# 780-00012-P1_rev3_Sch_M2_Focus_Drive.net
KiCad netlist of a schematic drawn in Altium Designer
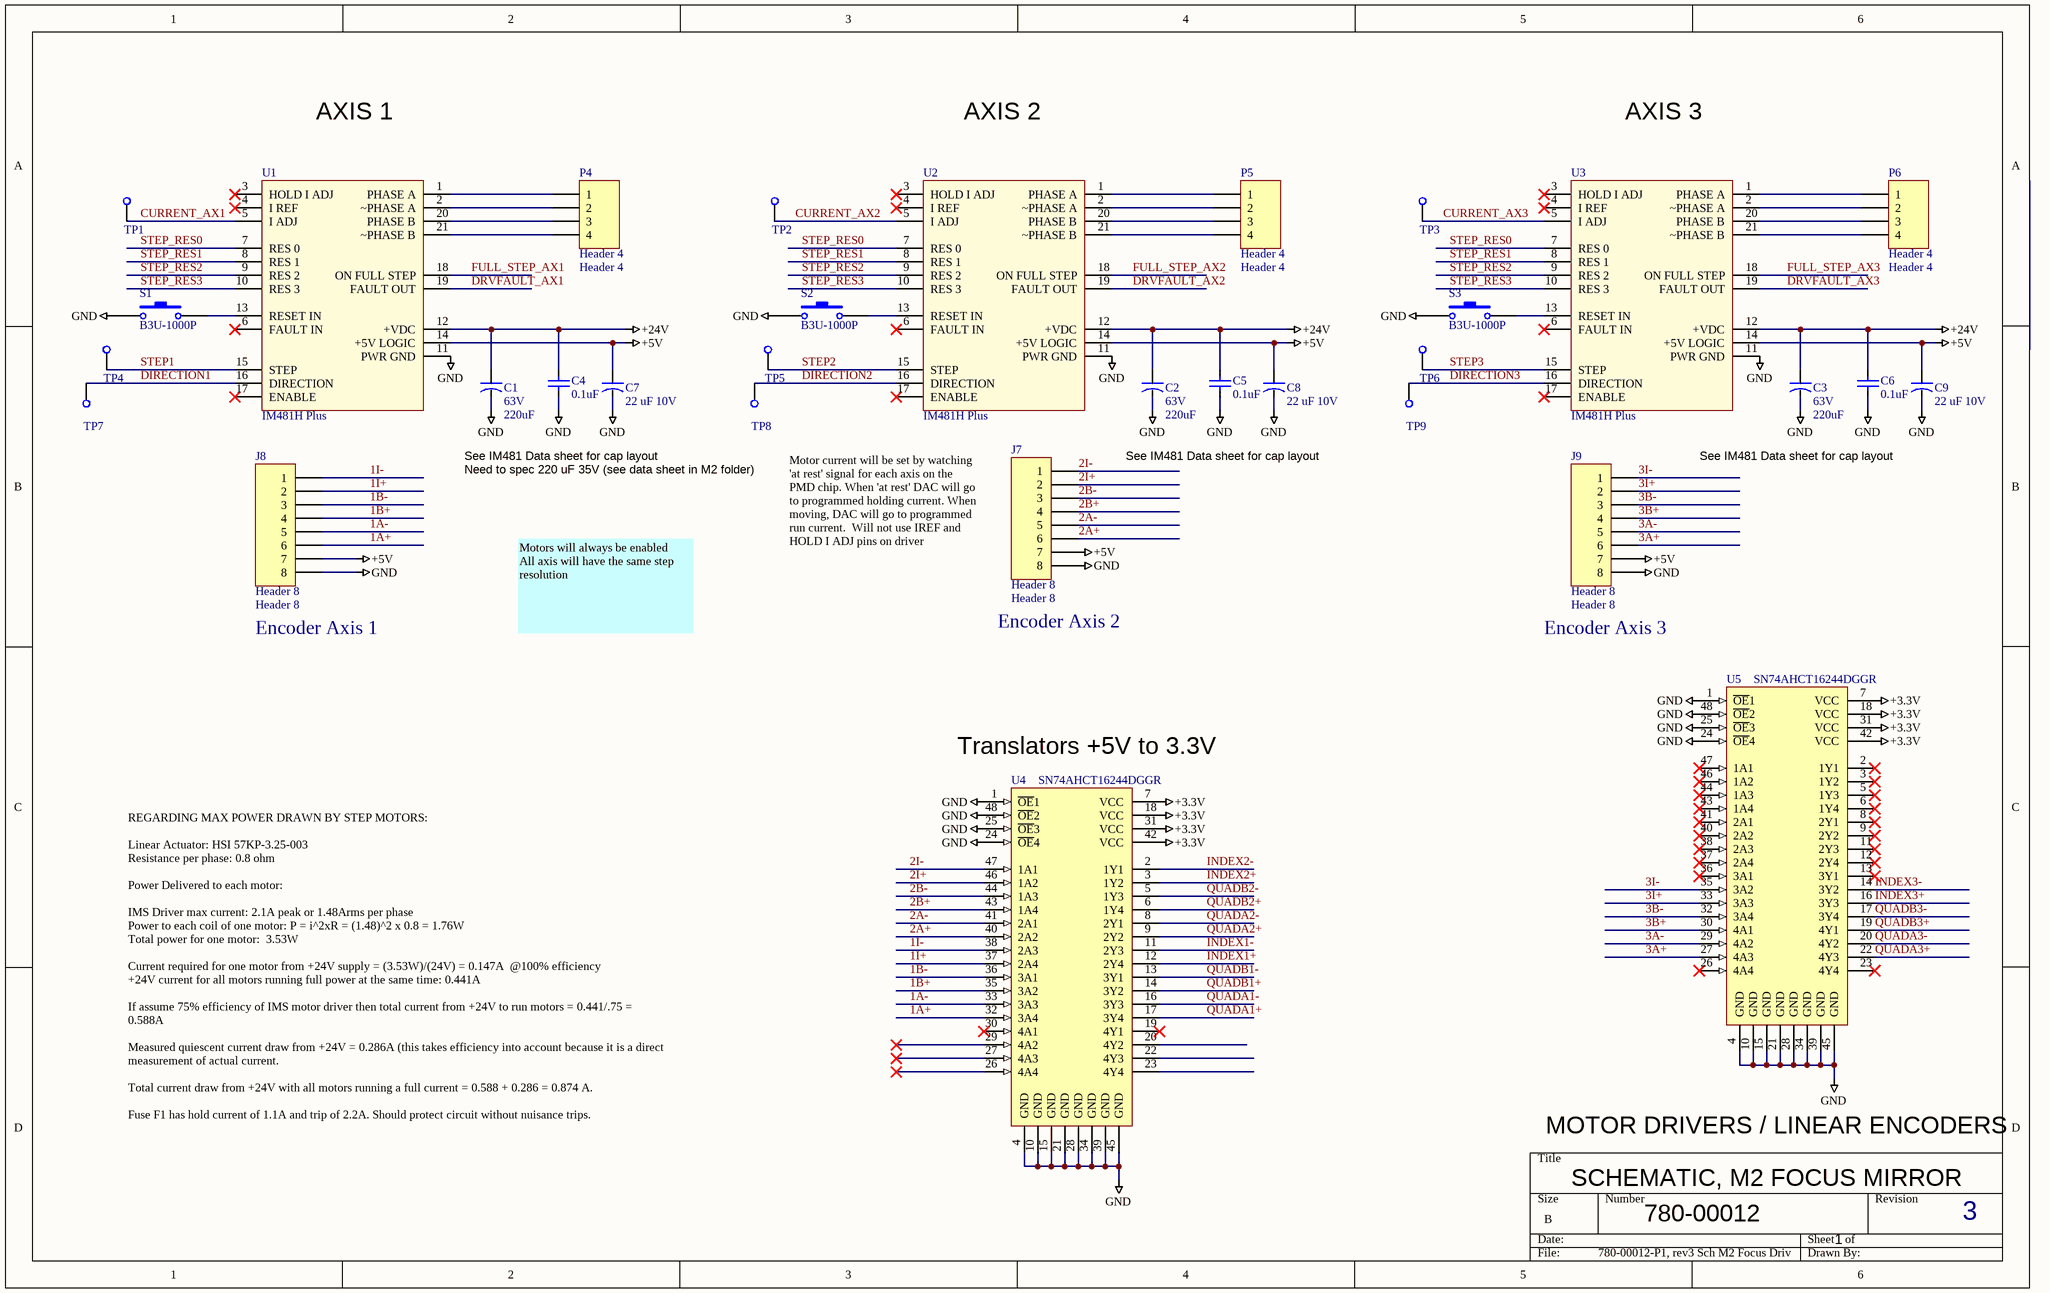
[diagram p0: 780-00012-P1, rev3 Sch M2 Focus Drive.SchDoc]

(export (version "E")
  (design (tool "Eeschema 10.0.6"))
  (components
    (comp (ref "C1")
      (value "63V")
      (footprint "CAP 220uF 63V")
      (description "CAP 220UF 63V ELECT MVH SMD")
      (fields (field (name "MANUFACTURER") "United Chemi-Con") (field (name "ALTIUM_VALUE") "220uF"))
      (libsource (lib "Richs Schematic Components") (part "Cap 220uF, 63V"))
    )
    (comp (ref "C2")
      (value "63V")
      (footprint "CAP 220uF 63V")
      (description "CAP 220UF 63V ELECT MVH SMD")
      (fields (field (name "MANUFACTURER") "United Chemi-Con") (field (name "ALTIUM_VALUE") "220uF"))
      (libsource (lib "Richs Schematic Components") (part "Cap 220uF, 63V"))
    )
    (comp (ref "C3")
      (value "63V")
      (footprint "CAP 220uF 63V")
      (description "CAP 220UF 63V ELECT MVH SMD")
      (fields (field (name "MANUFACTURER") "United Chemi-Con") (field (name "ALTIUM_VALUE") "220uF"))
      (libsource (lib "Richs Schematic Components") (part "Cap 220uF, 63V"))
    )
    (comp (ref "C4")
      (value "0.1uF")
      (footprint "SMD_0805")
      (description "Capacitor")
      (fields (field (name "Comment") "Cap SMD"))
      (libsource (lib "Richs Schematic Components") (part "Cap SMD"))
    )
    (comp (ref "C5")
      (value "0.1uF")
      (footprint "SMD_0805")
      (description "Capacitor")
      (fields (field (name "Comment") "Cap SMD"))
      (libsource (lib "Richs Schematic Components") (part "Cap SMD"))
    )
    (comp (ref "C6")
      (value "0.1uF")
      (footprint "SMD_0805")
      (description "Capacitor")
      (fields (field (name "Comment") "Cap SMD"))
      (libsource (lib "Richs Schematic Components") (part "Cap SMD"))
    )
    (comp (ref "C7")
      (value "22 uF 10V")
      (footprint "SMD_CAP_3216")
      (description "outline 3.2mm x 1.6mm")
      (fields (field (name "MANUFACTURER") "KEMET") (field (name "Comment") "16V"))
      (libsource (lib "Richs Schematic Components") (part "Cap Tant 16V"))
    )
    (comp (ref "C8")
      (value "22 uF 10V")
      (footprint "SMD_CAP_3216")
      (description "outline 3.2mm x 1.6mm")
      (fields (field (name "MANUFACTURER") "KEMET") (field (name "Comment") "16V"))
      (libsource (lib "Richs Schematic Components") (part "Cap Tant 16V"))
    )
    (comp (ref "C9")
      (value "22 uF 10V")
      (footprint "SMD_CAP_3216")
      (description "outline 3.2mm x 1.6mm")
      (fields (field (name "MANUFACTURER") "KEMET") (field (name "Comment") "16V"))
      (libsource (lib "Richs Schematic Components") (part "Cap Tant 16V"))
    )
    (comp (ref "J7")
      (value "Header 8")
      (footprint "HDR1X8 for IDC")
      (description "Header, 8-Pin")
      (fields (field (name "ALTIUM_VALUE") "Header 8"))
      (libsource (lib "Richs Schematic Components") (part "Header 8"))
    )
    (comp (ref "J8")
      (value "Header 8")
      (footprint "HDR1X8 for IDC")
      (description "Header, 8-Pin")
      (fields (field (name "ALTIUM_VALUE") "Header 8"))
      (libsource (lib "Richs Schematic Components") (part "Header 8"))
    )
    (comp (ref "J9")
      (value "Header 8")
      (footprint "HDR1X8 for IDC")
      (description "Header, 8-Pin")
      (fields (field (name "ALTIUM_VALUE") "Header 8"))
      (libsource (lib "Richs Schematic Components") (part "Header 8"))
    )
    (comp (ref "P4")
      (value "Header 4")
      (footprint "HDR1X4 for IDC")
      (description "Header, 4-Pin")
      (fields (field (name "ALTIUM_VALUE") "Header 4"))
      (libsource (lib "Richs Schematic Components") (part "Header 4"))
    )
    (comp (ref "P5")
      (value "Header 4")
      (footprint "HDR1X4 for IDC")
      (description "Header, 4-Pin")
      (fields (field (name "ALTIUM_VALUE") "Header 4"))
      (libsource (lib "Richs Schematic Components") (part "Header 4"))
    )
    (comp (ref "P6")
      (value "Header 4")
      (footprint "HDR1X4 for IDC")
      (description "Header, 4-Pin")
      (fields (field (name "ALTIUM_VALUE") "Header 4"))
      (libsource (lib "Richs Schematic Components") (part "Header 4"))
    )
    (comp (ref "S1")
      (value "B3U-1000P")
      (footprint "B3U-1000P")
      (description "Switch")
      (fields (field (name "MANUFACTURER") "Omron Electronics"))
      (libsource (lib "Miscellaneous Devices") (part "SW-PB"))
    )
    (comp (ref "S2")
      (value "B3U-1000P")
      (footprint "B3U-1000P")
      (description "Switch")
      (fields (field (name "MANUFACTURER") "Omron Electronics"))
      (libsource (lib "Miscellaneous Devices") (part "SW-PB"))
    )
    (comp (ref "S3")
      (value "B3U-1000P")
      (footprint "B3U-1000P")
      (description "Switch")
      (fields (field (name "MANUFACTURER") "Omron Electronics"))
      (libsource (lib "Miscellaneous Devices") (part "SW-PB"))
    )
    (comp (ref "TP1")
      (value "Test Point SMD")
      (footprint "SMD_TEST POINT")
      (description "SMD loop test point")
      (libsource (lib "Richs Schematic Components") (part "Test Point SMD"))
    )
    (comp (ref "TP2")
      (value "Test Point SMD")
      (footprint "SMD_TEST POINT")
      (description "SMD loop test point")
      (libsource (lib "Richs Schematic Components") (part "Test Point SMD"))
    )
    (comp (ref "TP3")
      (value "Test Point SMD")
      (footprint "SMD_TEST POINT")
      (description "SMD loop test point")
      (libsource (lib "Richs Schematic Components") (part "Test Point SMD"))
    )
    (comp (ref "TP4")
      (value "Test Point SMD")
      (footprint "SMD_TEST POINT")
      (description "SMD loop test point")
      (libsource (lib "Richs Schematic Components") (part "Test Point SMD"))
    )
    (comp (ref "TP5")
      (value "Test Point SMD")
      (footprint "SMD_TEST POINT")
      (description "SMD loop test point")
      (libsource (lib "Richs Schematic Components") (part "Test Point SMD"))
    )
    (comp (ref "TP6")
      (value "Test Point SMD")
      (footprint "SMD_TEST POINT")
      (description "SMD loop test point")
      (libsource (lib "Richs Schematic Components") (part "Test Point SMD"))
    )
    (comp (ref "TP7")
      (value "Test Point SMD")
      (footprint "SMD_TEST POINT")
      (description "SMD loop test point")
      (libsource (lib "Richs Schematic Components") (part "Test Point SMD"))
    )
    (comp (ref "TP8")
      (value "Test Point SMD")
      (footprint "SMD_TEST POINT")
      (description "SMD loop test point")
      (libsource (lib "Richs Schematic Components") (part "Test Point SMD"))
    )
    (comp (ref "TP9")
      (value "Test Point SMD")
      (footprint "SMD_TEST POINT")
      (description "SMD loop test point")
      (libsource (lib "Richs Schematic Components") (part "Test Point SMD"))
    )
    (comp (ref "U1")
      (value "IM481H Plus")
      (footprint "IM481H Vertical")
      (description "Hybrid stepper motor driver")
      (libsource (lib "Richs Schematic Components") (part "IM481H Plus"))
    )
    (comp (ref "U2")
      (value "IM481H Plus")
      (footprint "IM481H Vertical")
      (description "Hybrid stepper motor driver")
      (libsource (lib "Richs Schematic Components") (part "IM481H Plus"))
    )
    (comp (ref "U3")
      (value "IM481H Plus")
      (footprint "IM481H Vertical")
      (description "Hybrid stepper motor driver")
      (libsource (lib "Richs Schematic Components") (part "IM481H Plus"))
    )
    (comp (ref "U4")
      (value "SN74AHCT16244DGGR")
      (footprint "DGG048_N")
      (description "16-Bit Buffer/Driver with 3-State Outputs")
      (libsource (lib "TI Logic Buffer Line Driver") (part "SN74AHCT16244DGGR"))
    )
    (comp (ref "U5")
      (value "SN74AHCT16244DGGR")
      (footprint "DGG048_N")
      (description "16-Bit Buffer/Driver with 3-State Outputs")
      (libsource (lib "TI Logic Buffer Line Driver") (part "SN74AHCT16244DGGR"))
    )
  )
  (nets
    (net (code "1") (name "+3.3V") (class "Default")
      (node (ref "U4") (pin "18") (pinfunction "VCC_18") (pintype "power_in"))
      (node (ref "U4") (pin "31") (pinfunction "VCC_31") (pintype "power_in"))
      (node (ref "U4") (pin "42") (pinfunction "VCC_42") (pintype "power_in"))
      (node (ref "U4") (pin "7") (pinfunction "VCC_7") (pintype "power_in"))
      (node (ref "U5") (pin "18") (pinfunction "VCC_18") (pintype "power_in"))
      (node (ref "U5") (pin "31") (pinfunction "VCC_31") (pintype "power_in"))
      (node (ref "U5") (pin "42") (pinfunction "VCC_42") (pintype "power_in"))
      (node (ref "U5") (pin "7") (pinfunction "VCC_7") (pintype "power_in"))
    )
    (net (code "2") (name "+5V") (class "Default")
      (node (ref "C7") (pin "1") (pinfunction "1_1") (pintype "passive"))
      (node (ref "C8") (pin "1") (pinfunction "1_1") (pintype "passive"))
      (node (ref "C9") (pin "1") (pinfunction "1_1") (pintype "passive"))
      (node (ref "J7") (pin "7") (pinfunction "7_7") (pintype "passive"))
      (node (ref "J8") (pin "7") (pinfunction "7_7") (pintype "passive"))
      (node (ref "J9") (pin "7") (pinfunction "7_7") (pintype "passive"))
      (node (ref "U1") (pin "14") (pinfunction "+5V_LOGIC_14") (pintype "passive"))
      (node (ref "U2") (pin "14") (pinfunction "+5V_LOGIC_14") (pintype "passive"))
      (node (ref "U3") (pin "14") (pinfunction "+5V_LOGIC_14") (pintype "passive"))
    )
    (net (code "3") (name "+24V") (class "Default")
      (node (ref "C1") (pin "1") (pinfunction "1_1") (pintype "passive"))
      (node (ref "C2") (pin "1") (pinfunction "1_1") (pintype "passive"))
      (node (ref "C3") (pin "1") (pinfunction "1_1") (pintype "passive"))
      (node (ref "C4") (pin "2") (pinfunction "2_2") (pintype "passive"))
      (node (ref "C5") (pin "2") (pinfunction "2_2") (pintype "passive"))
      (node (ref "C6") (pin "2") (pinfunction "2_2") (pintype "passive"))
      (node (ref "U1") (pin "12") (pinfunction "+VDC_12") (pintype "passive"))
      (node (ref "U2") (pin "12") (pinfunction "+VDC_12") (pintype "passive"))
      (node (ref "U3") (pin "12") (pinfunction "+VDC_12") (pintype "passive"))
    )
    (net (code "4") (name "/1A+") (class "Default")
      (node (ref "J8") (pin "6") (pinfunction "6_6") (pintype "passive"))
      (node (ref "U4") (pin "32") (pinfunction "3A4_32") (pintype "input"))
    )
    (net (code "5") (name "/1A-") (class "Default")
      (node (ref "J8") (pin "5") (pinfunction "5_5") (pintype "passive"))
      (node (ref "U4") (pin "33") (pinfunction "3A3_33") (pintype "input"))
    )
    (net (code "6") (name "/1B+") (class "Default")
      (node (ref "J8") (pin "4") (pinfunction "4_4") (pintype "passive"))
      (node (ref "U4") (pin "35") (pinfunction "3A2_35") (pintype "input"))
    )
    (net (code "7") (name "/1B-") (class "Default")
      (node (ref "J8") (pin "3") (pinfunction "3_3") (pintype "passive"))
      (node (ref "U4") (pin "36") (pinfunction "3A1_36") (pintype "input"))
    )
    (net (code "8") (name "/1I+") (class "Default")
      (node (ref "J8") (pin "2") (pinfunction "2_2") (pintype "passive"))
      (node (ref "U4") (pin "37") (pinfunction "2A4_37") (pintype "input"))
    )
    (net (code "9") (name "/1I-") (class "Default")
      (node (ref "J8") (pin "1") (pinfunction "1_1") (pintype "passive"))
      (node (ref "U4") (pin "38") (pinfunction "2A3_38") (pintype "input"))
    )
    (net (code "10") (name "/2A+") (class "Default")
      (node (ref "J7") (pin "6") (pinfunction "6_6") (pintype "passive"))
      (node (ref "U4") (pin "40") (pinfunction "2A2_40") (pintype "input"))
    )
    (net (code "11") (name "/2A-") (class "Default")
      (node (ref "J7") (pin "5") (pinfunction "5_5") (pintype "passive"))
      (node (ref "U4") (pin "41") (pinfunction "2A1_41") (pintype "input"))
    )
    (net (code "12") (name "/2B+") (class "Default")
      (node (ref "J7") (pin "4") (pinfunction "4_4") (pintype "passive"))
      (node (ref "U4") (pin "43") (pinfunction "1A4_43") (pintype "input"))
    )
    (net (code "13") (name "/2B-") (class "Default")
      (node (ref "J7") (pin "3") (pinfunction "3_3") (pintype "passive"))
      (node (ref "U4") (pin "44") (pinfunction "1A3_44") (pintype "input"))
    )
    (net (code "14") (name "/2I+") (class "Default")
      (node (ref "J7") (pin "2") (pinfunction "2_2") (pintype "passive"))
      (node (ref "U4") (pin "46") (pinfunction "1A2_46") (pintype "input"))
    )
    (net (code "15") (name "/2I-") (class "Default")
      (node (ref "J7") (pin "1") (pinfunction "1_1") (pintype "passive"))
      (node (ref "U4") (pin "47") (pinfunction "1A1_47") (pintype "input"))
    )
    (net (code "16") (name "/3A+") (class "Default")
      (node (ref "J9") (pin "6") (pinfunction "6_6") (pintype "passive"))
      (node (ref "U5") (pin "27") (pinfunction "4A3_27") (pintype "input"))
    )
    (net (code "17") (name "/3A-") (class "Default")
      (node (ref "J9") (pin "5") (pinfunction "5_5") (pintype "passive"))
      (node (ref "U5") (pin "29") (pinfunction "4A2_29") (pintype "input"))
    )
    (net (code "18") (name "/3B+") (class "Default")
      (node (ref "J9") (pin "4") (pinfunction "4_4") (pintype "passive"))
      (node (ref "U5") (pin "30") (pinfunction "4A1_30") (pintype "input"))
    )
    (net (code "19") (name "/3B-") (class "Default")
      (node (ref "J9") (pin "3") (pinfunction "3_3") (pintype "passive"))
      (node (ref "U5") (pin "32") (pinfunction "3A4_32") (pintype "input"))
    )
    (net (code "20") (name "/3I+") (class "Default")
      (node (ref "J9") (pin "2") (pinfunction "2_2") (pintype "passive"))
      (node (ref "U5") (pin "33") (pinfunction "3A3_33") (pintype "input"))
    )
    (net (code "21") (name "/3I-") (class "Default")
      (node (ref "J9") (pin "1") (pinfunction "1_1") (pintype "passive"))
      (node (ref "U5") (pin "35") (pinfunction "3A2_35") (pintype "input"))
    )
    (net (code "22") (name "/CURRENT_AX1") (class "Default")
      (node (ref "TP1") (pin "1") (pinfunction "TP_1") (pintype "passive"))
      (node (ref "U1") (pin "5") (pinfunction "I_ADJ_5") (pintype "passive"))
    )
    (net (code "23") (name "/CURRENT_AX2") (class "Default")
      (node (ref "TP2") (pin "1") (pinfunction "TP_1") (pintype "passive"))
      (node (ref "U2") (pin "5") (pinfunction "I_ADJ_5") (pintype "passive"))
    )
    (net (code "24") (name "/CURRENT_AX3") (class "Default")
      (node (ref "TP3") (pin "1") (pinfunction "TP_1") (pintype "passive"))
      (node (ref "U3") (pin "5") (pinfunction "I_ADJ_5") (pintype "passive"))
    )
    (net (code "25") (name "/DIRECTION1") (class "Default")
      (node (ref "TP7") (pin "1") (pinfunction "TP_1") (pintype "passive"))
      (node (ref "U1") (pin "16") (pinfunction "DIRECTION_16") (pintype "passive"))
    )
    (net (code "26") (name "/DIRECTION2") (class "Default")
      (node (ref "TP8") (pin "1") (pinfunction "TP_1") (pintype "passive"))
      (node (ref "U2") (pin "16") (pinfunction "DIRECTION_16") (pintype "passive"))
    )
    (net (code "27") (name "/DIRECTION3") (class "Default")
      (node (ref "TP9") (pin "1") (pinfunction "TP_1") (pintype "passive"))
      (node (ref "U3") (pin "16") (pinfunction "DIRECTION_16") (pintype "passive"))
    )
    (net (code "28") (name "/DRVFAULT_AX1") (class "Default")
      (node (ref "U1") (pin "19") (pinfunction "FAULT_OUT_19") (pintype "passive"))
    )
    (net (code "29") (name "/DRVFAULT_AX2") (class "Default")
      (node (ref "U2") (pin "19") (pinfunction "FAULT_OUT_19") (pintype "passive"))
    )
    (net (code "30") (name "/DRVFAULT_AX3") (class "Default")
      (node (ref "U3") (pin "19") (pinfunction "FAULT_OUT_19") (pintype "passive"))
    )
    (net (code "31") (name "/FULL_STEP_AX1") (class "Default")
      (node (ref "U1") (pin "18") (pinfunction "ON_FULL_STEP_18") (pintype "passive"))
    )
    (net (code "32") (name "/FULL_STEP_AX2") (class "Default")
      (node (ref "U2") (pin "18") (pinfunction "ON_FULL_STEP_18") (pintype "passive"))
    )
    (net (code "33") (name "/FULL_STEP_AX3") (class "Default")
      (node (ref "U3") (pin "18") (pinfunction "ON_FULL_STEP_18") (pintype "passive"))
    )
    (net (code "34") (name "/INDEX1+") (class "Default")
      (node (ref "U4") (pin "12") (pinfunction "2Y4_12") (pintype "tri_state"))
    )
    (net (code "35") (name "/INDEX1-") (class "Default")
      (node (ref "U4") (pin "11") (pinfunction "2Y3_11") (pintype "tri_state"))
    )
    (net (code "36") (name "/INDEX2+") (class "Default")
      (node (ref "U4") (pin "3") (pinfunction "1Y2_3") (pintype "tri_state"))
    )
    (net (code "37") (name "/INDEX2-") (class "Default")
      (node (ref "U4") (pin "2") (pinfunction "1Y1_2") (pintype "tri_state"))
    )
    (net (code "38") (name "/INDEX3+") (class "Default")
      (node (ref "U5") (pin "16") (pinfunction "3Y3_16") (pintype "tri_state"))
    )
    (net (code "39") (name "/INDEX3-") (class "Default")
      (node (ref "U5") (pin "14") (pinfunction "3Y2_14") (pintype "tri_state"))
    )
    (net (code "40") (name "/QUADA1+") (class "Default")
      (node (ref "U4") (pin "17") (pinfunction "3Y4_17") (pintype "tri_state"))
    )
    (net (code "41") (name "/QUADA1-") (class "Default")
      (node (ref "U4") (pin "16") (pinfunction "3Y3_16") (pintype "tri_state"))
    )
    (net (code "42") (name "/QUADA2+") (class "Default")
      (node (ref "U4") (pin "9") (pinfunction "2Y2_9") (pintype "tri_state"))
    )
    (net (code "43") (name "/QUADA2-") (class "Default")
      (node (ref "U4") (pin "8") (pinfunction "2Y1_8") (pintype "tri_state"))
    )
    (net (code "44") (name "/QUADA3+") (class "Default")
      (node (ref "U5") (pin "22") (pinfunction "4Y3_22") (pintype "tri_state"))
    )
    (net (code "45") (name "/QUADA3-") (class "Default")
      (node (ref "U5") (pin "20") (pinfunction "4Y2_20") (pintype "tri_state"))
    )
    (net (code "46") (name "/QUADB1+") (class "Default")
      (node (ref "U4") (pin "14") (pinfunction "3Y2_14") (pintype "tri_state"))
    )
    (net (code "47") (name "/QUADB1-") (class "Default")
      (node (ref "U4") (pin "13") (pinfunction "3Y1_13") (pintype "tri_state"))
    )
    (net (code "48") (name "/QUADB2+") (class "Default")
      (node (ref "U4") (pin "6") (pinfunction "1Y4_6") (pintype "tri_state"))
    )
    (net (code "49") (name "/QUADB2-") (class "Default")
      (node (ref "U4") (pin "5") (pinfunction "1Y3_5") (pintype "tri_state"))
    )
    (net (code "50") (name "/QUADB3+") (class "Default")
      (node (ref "U5") (pin "19") (pinfunction "4Y1_19") (pintype "tri_state"))
    )
    (net (code "51") (name "/QUADB3-") (class "Default")
      (node (ref "U5") (pin "17") (pinfunction "3Y4_17") (pintype "tri_state"))
    )
    (net (code "52") (name "/STEP1") (class "Default")
      (node (ref "TP4") (pin "1") (pinfunction "TP_1") (pintype "passive"))
      (node (ref "U1") (pin "15") (pinfunction "STEP_15") (pintype "passive"))
    )
    (net (code "53") (name "/STEP2") (class "Default")
      (node (ref "TP5") (pin "1") (pinfunction "TP_1") (pintype "passive"))
      (node (ref "U2") (pin "15") (pinfunction "STEP_15") (pintype "passive"))
    )
    (net (code "54") (name "/STEP3") (class "Default")
      (node (ref "TP6") (pin "1") (pinfunction "TP_1") (pintype "passive"))
      (node (ref "U3") (pin "15") (pinfunction "STEP_15") (pintype "passive"))
    )
    (net (code "55") (name "/STEP_RES0") (class "Default")
      (node (ref "U1") (pin "7") (pinfunction "RES_0_7") (pintype "passive"))
      (node (ref "U2") (pin "7") (pinfunction "RES_0_7") (pintype "passive"))
      (node (ref "U3") (pin "7") (pinfunction "RES_0_7") (pintype "passive"))
    )
    (net (code "56") (name "/STEP_RES1") (class "Default")
      (node (ref "U1") (pin "8") (pinfunction "RES_1_8") (pintype "passive"))
      (node (ref "U2") (pin "8") (pinfunction "RES_1_8") (pintype "passive"))
      (node (ref "U3") (pin "8") (pinfunction "RES_1_8") (pintype "passive"))
    )
    (net (code "57") (name "/STEP_RES2") (class "Default")
      (node (ref "U1") (pin "9") (pinfunction "RES_2_9") (pintype "passive"))
      (node (ref "U2") (pin "9") (pinfunction "RES_2_9") (pintype "passive"))
      (node (ref "U3") (pin "9") (pinfunction "RES_2_9") (pintype "passive"))
    )
    (net (code "58") (name "/STEP_RES3") (class "Default")
      (node (ref "U1") (pin "10") (pinfunction "RES_3_10") (pintype "passive"))
      (node (ref "U2") (pin "10") (pinfunction "RES_3_10") (pintype "passive"))
      (node (ref "U3") (pin "10") (pinfunction "RES_3_10") (pintype "passive"))
    )
    (net (code "59") (name "GND") (class "Default")
      (node (ref "C1") (pin "2") (pinfunction "2_2") (pintype "passive"))
      (node (ref "C2") (pin "2") (pinfunction "2_2") (pintype "passive"))
      (node (ref "C3") (pin "2") (pinfunction "2_2") (pintype "passive"))
      (node (ref "C4") (pin "1") (pinfunction "1_1") (pintype "passive"))
      (node (ref "C5") (pin "1") (pinfunction "1_1") (pintype "passive"))
      (node (ref "C6") (pin "1") (pinfunction "1_1") (pintype "passive"))
      (node (ref "C7") (pin "2") (pinfunction "2_2") (pintype "passive"))
      (node (ref "C8") (pin "2") (pinfunction "2_2") (pintype "passive"))
      (node (ref "C9") (pin "2") (pinfunction "2_2") (pintype "passive"))
      (node (ref "J7") (pin "8") (pinfunction "8_8") (pintype "passive"))
      (node (ref "J8") (pin "8") (pinfunction "8_8") (pintype "passive"))
      (node (ref "J9") (pin "8") (pinfunction "8_8") (pintype "passive"))
      (node (ref "S1") (pin "1") (pinfunction "1_1") (pintype "passive"))
      (node (ref "S2") (pin "1") (pinfunction "1_1") (pintype "passive"))
      (node (ref "S3") (pin "1") (pinfunction "1_1") (pintype "passive"))
      (node (ref "U1") (pin "11") (pinfunction "PWR_GND_11") (pintype "passive"))
      (node (ref "U2") (pin "11") (pinfunction "PWR_GND_11") (pintype "passive"))
      (node (ref "U3") (pin "11") (pinfunction "PWR_GND_11") (pintype "passive"))
      (node (ref "U4") (pin "1") (pinfunction "~{OE}1_1") (pintype "input"))
      (node (ref "U4") (pin "10") (pinfunction "GND_10") (pintype "power_in"))
      (node (ref "U4") (pin "15") (pinfunction "GND_15") (pintype "power_in"))
      (node (ref "U4") (pin "21") (pinfunction "GND_21") (pintype "power_in"))
      (node (ref "U4") (pin "24") (pinfunction "~{OE}4_24") (pintype "input"))
      (node (ref "U4") (pin "25") (pinfunction "~{OE}3_25") (pintype "input"))
      (node (ref "U4") (pin "28") (pinfunction "GND_28") (pintype "power_in"))
      (node (ref "U4") (pin "34") (pinfunction "GND_34") (pintype "power_in"))
      (node (ref "U4") (pin "39") (pinfunction "GND_39") (pintype "power_in"))
      (node (ref "U4") (pin "4") (pinfunction "GND_4") (pintype "power_in"))
      (node (ref "U4") (pin "45") (pinfunction "GND_45") (pintype "power_in"))
      (node (ref "U4") (pin "48") (pinfunction "~{OE}2_48") (pintype "input"))
      (node (ref "U5") (pin "1") (pinfunction "~{OE}1_1") (pintype "input"))
      (node (ref "U5") (pin "10") (pinfunction "GND_10") (pintype "power_in"))
      (node (ref "U5") (pin "15") (pinfunction "GND_15") (pintype "power_in"))
      (node (ref "U5") (pin "21") (pinfunction "GND_21") (pintype "power_in"))
      (node (ref "U5") (pin "24") (pinfunction "~{OE}4_24") (pintype "input"))
      (node (ref "U5") (pin "25") (pinfunction "~{OE}3_25") (pintype "input"))
      (node (ref "U5") (pin "28") (pinfunction "GND_28") (pintype "power_in"))
      (node (ref "U5") (pin "34") (pinfunction "GND_34") (pintype "power_in"))
      (node (ref "U5") (pin "39") (pinfunction "GND_39") (pintype "power_in"))
      (node (ref "U5") (pin "4") (pinfunction "GND_4") (pintype "power_in"))
      (node (ref "U5") (pin "45") (pinfunction "GND_45") (pintype "power_in"))
      (node (ref "U5") (pin "48") (pinfunction "~{OE}2_48") (pintype "input"))
    )
    (net (code "60") (name "Net-(U1-PHASE_A)") (class "Default")
      (node (ref "P4") (pin "1") (pinfunction "1_1") (pintype "passive"))
      (node (ref "U1") (pin "1") (pinfunction "PHASE_A_1") (pintype "passive"))
    )
    (net (code "61") (name "Net-(U1-PHASE_B)") (class "Default")
      (node (ref "P4") (pin "3") (pinfunction "3_3") (pintype "passive"))
      (node (ref "U1") (pin "20") (pinfunction "PHASE_B_20") (pintype "passive"))
    )
    (net (code "62") (name "Net-(U1-RESET_IN)") (class "Default")
      (node (ref "S1") (pin "2") (pinfunction "2_2") (pintype "passive"))
      (node (ref "U1") (pin "13") (pinfunction "RESET_IN_13") (pintype "passive"))
    )
    (net (code "63") (name "Net-(U1-~PHASE_A)") (class "Default")
      (node (ref "P4") (pin "2") (pinfunction "2_2") (pintype "passive"))
      (node (ref "U1") (pin "2") (pinfunction "~PHASE_A_2") (pintype "passive"))
    )
    (net (code "64") (name "Net-(U1-~PHASE_B)") (class "Default")
      (node (ref "P4") (pin "4") (pinfunction "4_4") (pintype "passive"))
      (node (ref "U1") (pin "21") (pinfunction "~PHASE_B_21") (pintype "passive"))
    )
    (net (code "65") (name "Net-(U2-PHASE_A)") (class "Default")
      (node (ref "P5") (pin "1") (pinfunction "1_1") (pintype "passive"))
      (node (ref "U2") (pin "1") (pinfunction "PHASE_A_1") (pintype "passive"))
    )
    (net (code "66") (name "Net-(U2-PHASE_B)") (class "Default")
      (node (ref "P5") (pin "3") (pinfunction "3_3") (pintype "passive"))
      (node (ref "U2") (pin "20") (pinfunction "PHASE_B_20") (pintype "passive"))
    )
    (net (code "67") (name "Net-(U2-RESET_IN)") (class "Default")
      (node (ref "S2") (pin "2") (pinfunction "2_2") (pintype "passive"))
      (node (ref "U2") (pin "13") (pinfunction "RESET_IN_13") (pintype "passive"))
    )
    (net (code "68") (name "Net-(U2-~PHASE_A)") (class "Default")
      (node (ref "P5") (pin "2") (pinfunction "2_2") (pintype "passive"))
      (node (ref "U2") (pin "2") (pinfunction "~PHASE_A_2") (pintype "passive"))
    )
    (net (code "69") (name "Net-(U2-~PHASE_B)") (class "Default")
      (node (ref "P5") (pin "4") (pinfunction "4_4") (pintype "passive"))
      (node (ref "U2") (pin "21") (pinfunction "~PHASE_B_21") (pintype "passive"))
    )
    (net (code "70") (name "Net-(U3-PHASE_A)") (class "Default")
      (node (ref "P6") (pin "1") (pinfunction "1_1") (pintype "passive"))
      (node (ref "U3") (pin "1") (pinfunction "PHASE_A_1") (pintype "passive"))
    )
    (net (code "71") (name "Net-(U3-PHASE_B)") (class "Default")
      (node (ref "P6") (pin "3") (pinfunction "3_3") (pintype "passive"))
      (node (ref "U3") (pin "20") (pinfunction "PHASE_B_20") (pintype "passive"))
    )
    (net (code "72") (name "Net-(U3-RESET_IN)") (class "Default")
      (node (ref "S3") (pin "2") (pinfunction "2_2") (pintype "passive"))
      (node (ref "U3") (pin "13") (pinfunction "RESET_IN_13") (pintype "passive"))
    )
    (net (code "73") (name "Net-(U3-~PHASE_A)") (class "Default")
      (node (ref "P6") (pin "2") (pinfunction "2_2") (pintype "passive"))
      (node (ref "U3") (pin "2") (pinfunction "~PHASE_A_2") (pintype "passive"))
    )
    (net (code "74") (name "Net-(U3-~PHASE_B)") (class "Default")
      (node (ref "P6") (pin "4") (pinfunction "4_4") (pintype "passive"))
      (node (ref "U3") (pin "21") (pinfunction "~PHASE_B_21") (pintype "passive"))
    )
    (net (code "75") (name "unconnected-(U1-ENABLE-Pad17)") (class "Default")
      (node (ref "U1") (pin "17") (pinfunction "ENABLE_17") (pintype "passive+no_connect"))
    )
    (net (code "76") (name "unconnected-(U1-FAULT_IN-Pad6)") (class "Default")
      (node (ref "U1") (pin "6") (pinfunction "FAULT_IN_6") (pintype "passive+no_connect"))
    )
    (net (code "77") (name "unconnected-(U1-HOLD_I_ADJ-Pad3)") (class "Default")
      (node (ref "U1") (pin "3") (pinfunction "HOLD_I_ADJ_3") (pintype "passive+no_connect"))
    )
    (net (code "78") (name "unconnected-(U1-I_REF-Pad4)") (class "Default")
      (node (ref "U1") (pin "4") (pinfunction "I_REF_4") (pintype "passive+no_connect"))
    )
    (net (code "79") (name "unconnected-(U2-ENABLE-Pad17)") (class "Default")
      (node (ref "U2") (pin "17") (pinfunction "ENABLE_17") (pintype "passive+no_connect"))
    )
    (net (code "80") (name "unconnected-(U2-FAULT_IN-Pad6)") (class "Default")
      (node (ref "U2") (pin "6") (pinfunction "FAULT_IN_6") (pintype "passive+no_connect"))
    )
    (net (code "81") (name "unconnected-(U2-HOLD_I_ADJ-Pad3)") (class "Default")
      (node (ref "U2") (pin "3") (pinfunction "HOLD_I_ADJ_3") (pintype "passive+no_connect"))
    )
    (net (code "82") (name "unconnected-(U2-I_REF-Pad4)") (class "Default")
      (node (ref "U2") (pin "4") (pinfunction "I_REF_4") (pintype "passive+no_connect"))
    )
    (net (code "83") (name "unconnected-(U3-ENABLE-Pad17)") (class "Default")
      (node (ref "U3") (pin "17") (pinfunction "ENABLE_17") (pintype "passive+no_connect"))
    )
    (net (code "84") (name "unconnected-(U3-FAULT_IN-Pad6)") (class "Default")
      (node (ref "U3") (pin "6") (pinfunction "FAULT_IN_6") (pintype "passive+no_connect"))
    )
    (net (code "85") (name "unconnected-(U3-HOLD_I_ADJ-Pad3)") (class "Default")
      (node (ref "U3") (pin "3") (pinfunction "HOLD_I_ADJ_3") (pintype "passive+no_connect"))
    )
    (net (code "86") (name "unconnected-(U3-I_REF-Pad4)") (class "Default")
      (node (ref "U3") (pin "4") (pinfunction "I_REF_4") (pintype "passive+no_connect"))
    )
    (net (code "87") (name "unconnected-(U4-4A1-Pad30)") (class "Default")
      (node (ref "U4") (pin "30") (pinfunction "4A1_30") (pintype "input+no_connect"))
    )
    (net (code "88") (name "unconnected-(U4-4A2-Pad29)") (class "Default")
      (node (ref "U4") (pin "29") (pinfunction "4A2_29") (pintype "input+no_connect"))
    )
    (net (code "89") (name "unconnected-(U4-4A3-Pad27)") (class "Default")
      (node (ref "U4") (pin "27") (pinfunction "4A3_27") (pintype "input+no_connect"))
    )
    (net (code "90") (name "unconnected-(U4-4A4-Pad26)") (class "Default")
      (node (ref "U4") (pin "26") (pinfunction "4A4_26") (pintype "input+no_connect"))
    )
    (net (code "91") (name "unconnected-(U4-4Y1-Pad19)") (class "Default")
      (node (ref "U4") (pin "19") (pinfunction "4Y1_19") (pintype "tri_state+no_connect"))
    )
    (net (code "92") (name "unconnected-(U4-4Y2-Pad20)") (class "Default")
      (node (ref "U4") (pin "20") (pinfunction "4Y2_20") (pintype "tri_state"))
    )
    (net (code "93") (name "unconnected-(U4-4Y3-Pad22)") (class "Default")
      (node (ref "U4") (pin "22") (pinfunction "4Y3_22") (pintype "tri_state"))
    )
    (net (code "94") (name "unconnected-(U4-4Y4-Pad23)") (class "Default")
      (node (ref "U4") (pin "23") (pinfunction "4Y4_23") (pintype "tri_state"))
    )
    (net (code "95") (name "unconnected-(U5-1A1-Pad47)") (class "Default")
      (node (ref "U5") (pin "47") (pinfunction "1A1_47") (pintype "input+no_connect"))
    )
    (net (code "96") (name "unconnected-(U5-1A2-Pad46)") (class "Default")
      (node (ref "U5") (pin "46") (pinfunction "1A2_46") (pintype "input+no_connect"))
    )
    (net (code "97") (name "unconnected-(U5-1A3-Pad44)") (class "Default")
      (node (ref "U5") (pin "44") (pinfunction "1A3_44") (pintype "input+no_connect"))
    )
    (net (code "98") (name "unconnected-(U5-1A4-Pad43)") (class "Default")
      (node (ref "U5") (pin "43") (pinfunction "1A4_43") (pintype "input+no_connect"))
    )
    (net (code "99") (name "unconnected-(U5-1Y1-Pad2)") (class "Default")
      (node (ref "U5") (pin "2") (pinfunction "1Y1_2") (pintype "tri_state+no_connect"))
    )
    (net (code "100") (name "unconnected-(U5-1Y2-Pad3)") (class "Default")
      (node (ref "U5") (pin "3") (pinfunction "1Y2_3") (pintype "tri_state+no_connect"))
    )
    (net (code "101") (name "unconnected-(U5-1Y3-Pad5)") (class "Default")
      (node (ref "U5") (pin "5") (pinfunction "1Y3_5") (pintype "tri_state+no_connect"))
    )
    (net (code "102") (name "unconnected-(U5-1Y4-Pad6)") (class "Default")
      (node (ref "U5") (pin "6") (pinfunction "1Y4_6") (pintype "tri_state+no_connect"))
    )
    (net (code "103") (name "unconnected-(U5-2A1-Pad41)") (class "Default")
      (node (ref "U5") (pin "41") (pinfunction "2A1_41") (pintype "input+no_connect"))
    )
    (net (code "104") (name "unconnected-(U5-2A2-Pad40)") (class "Default")
      (node (ref "U5") (pin "40") (pinfunction "2A2_40") (pintype "input+no_connect"))
    )
    (net (code "105") (name "unconnected-(U5-2A3-Pad38)") (class "Default")
      (node (ref "U5") (pin "38") (pinfunction "2A3_38") (pintype "input+no_connect"))
    )
    (net (code "106") (name "unconnected-(U5-2A4-Pad37)") (class "Default")
      (node (ref "U5") (pin "37") (pinfunction "2A4_37") (pintype "input+no_connect"))
    )
    (net (code "107") (name "unconnected-(U5-2Y1-Pad8)") (class "Default")
      (node (ref "U5") (pin "8") (pinfunction "2Y1_8") (pintype "tri_state+no_connect"))
    )
    (net (code "108") (name "unconnected-(U5-2Y2-Pad9)") (class "Default")
      (node (ref "U5") (pin "9") (pinfunction "2Y2_9") (pintype "tri_state+no_connect"))
    )
    (net (code "109") (name "unconnected-(U5-2Y3-Pad11)") (class "Default")
      (node (ref "U5") (pin "11") (pinfunction "2Y3_11") (pintype "tri_state+no_connect"))
    )
    (net (code "110") (name "unconnected-(U5-2Y4-Pad12)") (class "Default")
      (node (ref "U5") (pin "12") (pinfunction "2Y4_12") (pintype "tri_state+no_connect"))
    )
    (net (code "111") (name "unconnected-(U5-3A1-Pad36)") (class "Default")
      (node (ref "U5") (pin "36") (pinfunction "3A1_36") (pintype "input+no_connect"))
    )
    (net (code "112") (name "unconnected-(U5-3Y1-Pad13)") (class "Default")
      (node (ref "U5") (pin "13") (pinfunction "3Y1_13") (pintype "tri_state+no_connect"))
    )
    (net (code "113") (name "unconnected-(U5-4A4-Pad26)") (class "Default")
      (node (ref "U5") (pin "26") (pinfunction "4A4_26") (pintype "input+no_connect"))
    )
    (net (code "114") (name "unconnected-(U5-4Y4-Pad23)") (class "Default")
      (node (ref "U5") (pin "23") (pinfunction "4Y4_23") (pintype "tri_state+no_connect"))
    )
  )
)
